# OSSILEDController.net
KiCad netlist of a schematic drawn in EAGLE
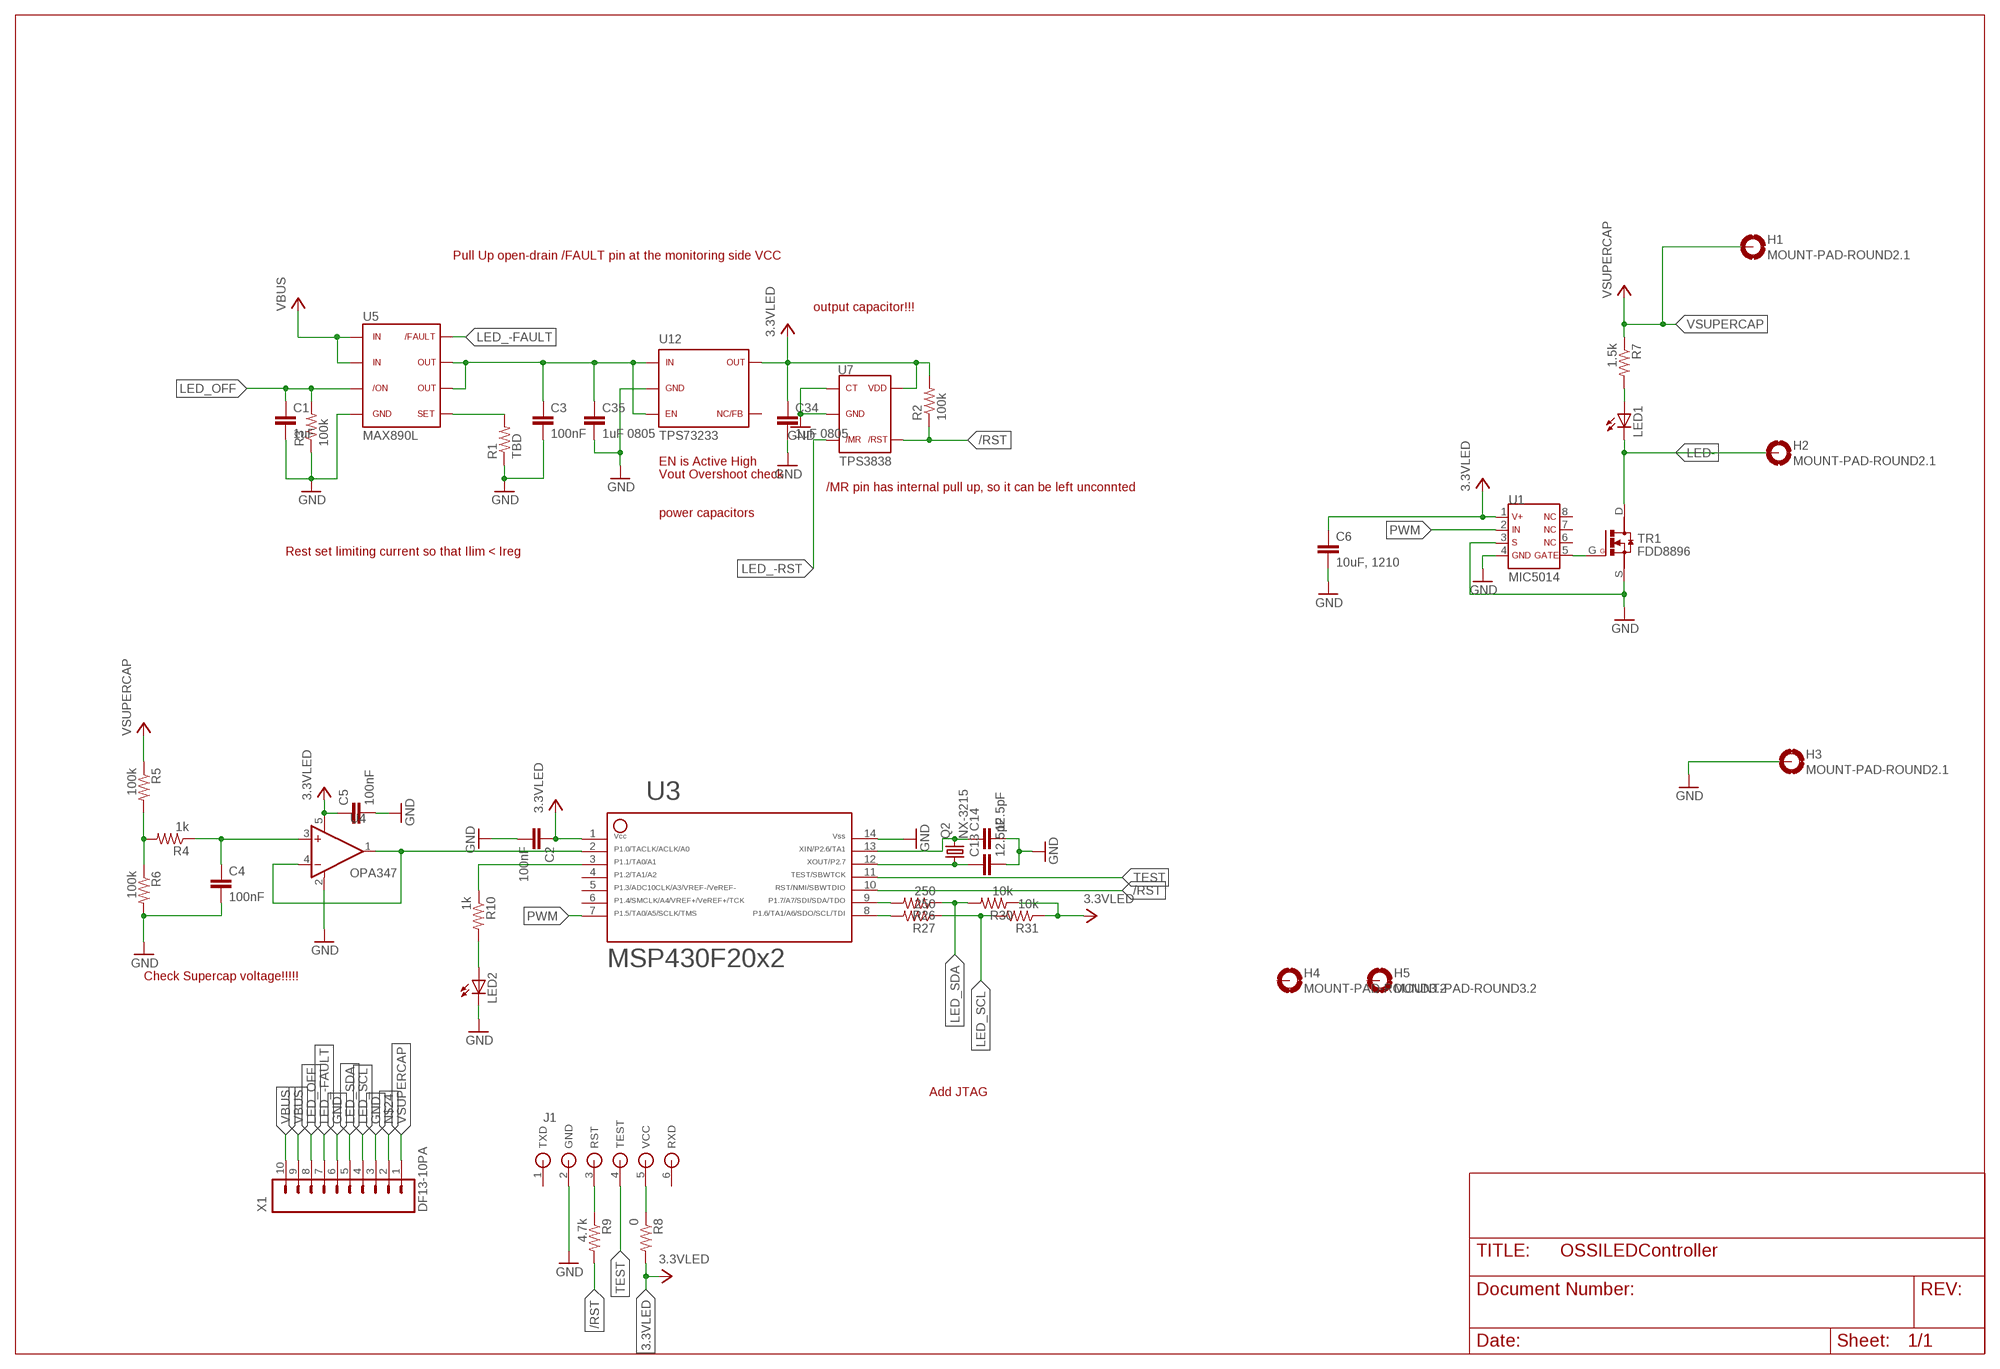
[diagram p0: schematic, sheet 1]

(export (version "E")
  (design (tool "Eeschema 10.0.6"))
  (components
    (comp (ref "C1")
      (value "1uF")
      (footprint "eagle-import:C0603(1608)")
      (libsource (lib "eagle-import") (part "C0603(1608)"))
    )
    (comp (ref "C2")
      (value "100nF")
      (footprint "eagle-import:C0603(1608)")
      (libsource (lib "eagle-import") (part "C0603(1608)"))
    )
    (comp (ref "C3")
      (value "100nF")
      (footprint "eagle-import:C0603(1608)")
      (libsource (lib "eagle-import") (part "C0603(1608)"))
    )
    (comp (ref "C4")
      (value "100nF")
      (footprint "eagle-import:C0603(1608)")
      (libsource (lib "eagle-import") (part "C0603(1608)"))
    )
    (comp (ref "C5")
      (value "100nF")
      (footprint "eagle-import:C0603(1608)")
      (libsource (lib "eagle-import") (part "C0603(1608)"))
    )
    (comp (ref "C6")
      (value "10uF, 1210")
      (footprint "eagle-import:C1210-GCM32")
      (libsource (lib "eagle-import") (part "C1210(3225)-GCM32"))
    )
    (comp (ref "C13")
      (value "12.5pF")
      (footprint "eagle-import:C0603(1608)")
      (libsource (lib "eagle-import") (part "C0603(1608)"))
    )
    (comp (ref "C14")
      (value "12.5pF")
      (footprint "eagle-import:C0603(1608)")
      (libsource (lib "eagle-import") (part "C0603(1608)"))
    )
    (comp (ref "C34")
      (value "1uF 0805")
      (footprint "eagle-import:C0805(2012)")
      (libsource (lib "eagle-import") (part "C0805(2012)"))
    )
    (comp (ref "C35")
      (value "1uF 0805")
      (footprint "eagle-import:C0805(2012)")
      (libsource (lib "eagle-import") (part "C0805(2012)"))
    )
    (comp (ref "H1")
      (value "MOUNT-PAD-ROUND2.1")
      (footprint "eagle-import:2.1-PAD-ROUND")
      (libsource (lib "eagle-import") (part "MOUNT-PAD-ROUND2.1"))
    )
    (comp (ref "H2")
      (value "MOUNT-PAD-ROUND2.1")
      (footprint "eagle-import:2.1-PAD-ROUND")
      (libsource (lib "eagle-import") (part "MOUNT-PAD-ROUND2.1"))
    )
    (comp (ref "H3")
      (value "MOUNT-PAD-ROUND2.1")
      (footprint "eagle-import:2.1-PAD-ROUND")
      (libsource (lib "eagle-import") (part "MOUNT-PAD-ROUND2.1"))
    )
    (comp (ref "H4")
      (value "MOUNT-PAD-ROUND3.2")
      (footprint "eagle-import:3.2-PAD-ROUND")
      (libsource (lib "eagle-import") (part "MOUNT-PAD-ROUND3.2"))
    )
    (comp (ref "H5")
      (value "MOUNT-PAD-ROUND3.2")
      (footprint "eagle-import:3.2-PAD-ROUND")
      (libsource (lib "eagle-import") (part "MOUNT-PAD-ROUND3.2"))
    )
    (comp (ref "J1")
      (value "JTAG-SBW-6")
      (footprint "eagle-import:SMD-PAD-6")
      (libsource (lib "eagle-import") (part "JTAG-SBW-6"))
    )
    (comp (ref "LED1")
      (value "LEDCHIPLED_0603")
      (footprint "eagle-import:CHIPLED_0603")
      (libsource (lib "eagle-import") (part "LEDCHIPLED_0603"))
    )
    (comp (ref "LED2")
      (value "LEDCHIPLED_0603")
      (footprint "eagle-import:CHIPLED_0603")
      (libsource (lib "eagle-import") (part "LEDCHIPLED_0603"))
    )
    (comp (ref "Q2")
      (value "NX-3215")
      (footprint "eagle-import:NX-3215")
      (libsource (lib "eagle-import") (part "NX-3215"))
    )
    (comp (ref "R1")
      (value "TBD")
      (footprint "eagle-import:R0603(1608)")
      (libsource (lib "eagle-import") (part "R0603(1608)"))
    )
    (comp (ref "R2")
      (value "100k")
      (footprint "eagle-import:R0603(1608)")
      (libsource (lib "eagle-import") (part "R0603(1608)"))
    )
    (comp (ref "R3")
      (value "100k")
      (footprint "eagle-import:R0603(1608)")
      (libsource (lib "eagle-import") (part "R0603(1608)"))
    )
    (comp (ref "R4")
      (value "1k")
      (footprint "eagle-import:R0603(1608)")
      (libsource (lib "eagle-import") (part "R0603(1608)"))
    )
    (comp (ref "R5")
      (value "100k")
      (footprint "eagle-import:R0603(1608)")
      (libsource (lib "eagle-import") (part "R0603(1608)"))
    )
    (comp (ref "R6")
      (value "100k")
      (footprint "eagle-import:R0603(1608)")
      (libsource (lib "eagle-import") (part "R0603(1608)"))
    )
    (comp (ref "R7")
      (value "1.5k")
      (footprint "eagle-import:R0603(1608)")
      (libsource (lib "eagle-import") (part "R0603(1608)"))
    )
    (comp (ref "R8")
      (value "0")
      (footprint "eagle-import:R0603(1608)")
      (libsource (lib "eagle-import") (part "R0603(1608)"))
    )
    (comp (ref "R9")
      (value "4.7k")
      (footprint "eagle-import:R0603(1608)")
      (libsource (lib "eagle-import") (part "R0603(1608)"))
    )
    (comp (ref "R10")
      (value "1k")
      (footprint "eagle-import:R0603(1608)")
      (libsource (lib "eagle-import") (part "R0603(1608)"))
    )
    (comp (ref "R26")
      (value "250")
      (footprint "eagle-import:R0603(1608)")
      (libsource (lib "eagle-import") (part "R0603(1608)"))
    )
    (comp (ref "R27")
      (value "250")
      (footprint "eagle-import:R0603(1608)")
      (libsource (lib "eagle-import") (part "R0603(1608)"))
    )
    (comp (ref "R30")
      (value "10k")
      (footprint "eagle-import:R0603(1608)")
      (libsource (lib "eagle-import") (part "R0603(1608)"))
    )
    (comp (ref "R31")
      (value "10k")
      (footprint "eagle-import:R0603(1608)")
      (libsource (lib "eagle-import") (part "R0603(1608)"))
    )
    (comp (ref "TR1")
      (value "FDD8896")
      (footprint "eagle-import:TO252")
      (libsource (lib "eagle-import") (part "FDD8896"))
    )
    (comp (ref "U1")
      (value "MIC5014")
      (footprint "eagle-import:SO8")
      (libsource (lib "eagle-import") (part "MIC5014"))
    )
    (comp (ref "U3")
      (value "MSP430F2012")
      (footprint "eagle-import:PW14")
      (libsource (lib "eagle-import") (part "MSP430F2012"))
    )
    (comp (ref "U4")
      (value "OPA347")
      (footprint "eagle-import:SOT23-5DBV")
      (libsource (lib "eagle-import") (part "OPA347"))
    )
    (comp (ref "U5")
      (value "MAX890L")
      (footprint "eagle-import:SO8")
      (libsource (lib "eagle-import") (part "MAX890L"))
    )
    (comp (ref "U7")
      (value "TPS3838")
      (footprint "eagle-import:SOT23-5DBV")
      (libsource (lib "eagle-import") (part "TPS3838"))
    )
    (comp (ref "U12")
      (value "TPS73233")
      (footprint "eagle-import:SOT23-5DBV")
      (libsource (lib "eagle-import") (part "TPS73233"))
    )
    (comp (ref "X1")
      (value "DF13-10PA")
      (footprint "eagle-import:DF13A-10P")
      (libsource (lib "eagle-import") (part "DF13-10PA"))
    )
  )
  (nets
    (net (code "1") (name "3.3VLED") (class "Default")
      (node (ref "C2") (pin "1") (pinfunction "1_1") (pintype "passive"))
      (node (ref "C34") (pin "1") (pinfunction "1_1") (pintype "passive"))
      (node (ref "C5") (pin "1") (pinfunction "1_1") (pintype "passive"))
      (node (ref "C6") (pin "P$1") (pinfunction "1_P$1") (pintype "passive"))
      (node (ref "R2") (pin "2") (pinfunction "2_2") (pintype "passive"))
      (node (ref "R30") (pin "1") (pinfunction "1_1") (pintype "passive"))
      (node (ref "R31") (pin "1") (pinfunction "1_1") (pintype "passive"))
      (node (ref "R8") (pin "2") (pinfunction "2_2") (pintype "passive"))
      (node (ref "U1") (pin "1") (pinfunction "P$1_1") (pintype "bidirectional"))
      (node (ref "U12") (pin "5") (pinfunction "5_5") (pintype "power_in"))
      (node (ref "U3") (pin "1") (pinfunction "1_1") (pintype "power_in"))
      (node (ref "U4") (pin "5") (pinfunction "V+_5") (pintype "power_in"))
      (node (ref "U7") (pin "5") (pinfunction "P$5_5") (pintype "power_in"))
    )
    (net (code "2") (name "GND") (class "Default")
      (node (ref "C1") (pin "2") (pinfunction "2_2") (pintype "passive"))
      (node (ref "C13") (pin "2") (pinfunction "2_2") (pintype "passive"))
      (node (ref "C14") (pin "2") (pinfunction "2_2") (pintype "passive"))
      (node (ref "C2") (pin "2") (pinfunction "2_2") (pintype "passive"))
      (node (ref "C3") (pin "2") (pinfunction "2_2") (pintype "passive"))
      (node (ref "C34") (pin "2") (pinfunction "2_2") (pintype "passive"))
      (node (ref "C35") (pin "2") (pinfunction "2_2") (pintype "passive"))
      (node (ref "C4") (pin "2") (pinfunction "2_2") (pintype "passive"))
      (node (ref "C5") (pin "2") (pinfunction "2_2") (pintype "passive"))
      (node (ref "C6") (pin "P$2") (pinfunction "2_P$2") (pintype "passive"))
      (node (ref "H3") (pin "B3,2") (pinfunction "MOUNT_B3,2") (pintype "passive"))
      (node (ref "J1") (pin "2") (pinfunction "GND_2") (pintype "bidirectional"))
      (node (ref "LED2") (pin "C") (pinfunction "C_C") (pintype "passive"))
      (node (ref "R1") (pin "1") (pinfunction "1_1") (pintype "passive"))
      (node (ref "R3") (pin "1") (pinfunction "1_1") (pintype "passive"))
      (node (ref "R6") (pin "2") (pinfunction "2_2") (pintype "passive"))
      (node (ref "TR1") (pin "S") (pinfunction "S_S") (pintype "bidirectional"))
      (node (ref "U1") (pin "3") (pinfunction "P$3_3") (pintype "bidirectional"))
      (node (ref "U1") (pin "4") (pinfunction "P$4_4") (pintype "bidirectional"))
      (node (ref "U12") (pin "2") (pinfunction "2_2") (pintype "power_in"))
      (node (ref "U3") (pin "14") (pinfunction "14_14") (pintype "power_in"))
      (node (ref "U4") (pin "2") (pinfunction "V-_2") (pintype "power_in"))
      (node (ref "U5") (pin "4") (pinfunction "P$4_4") (pintype "power_in"))
      (node (ref "U7") (pin "1") (pinfunction "P$1_1") (pintype "bidirectional"))
      (node (ref "U7") (pin "2") (pinfunction "P$2_2") (pintype "power_in"))
      (node (ref "X1") (pin "3") (pinfunction "3_3") (pintype "passive"))
      (node (ref "X1") (pin "6") (pinfunction "6_6") (pintype "passive"))
    )
    (net (code "3") (name "LED-") (class "Default")
      (node (ref "H2") (pin "B3,2") (pinfunction "MOUNT_B3,2") (pintype "passive"))
      (node (ref "LED1") (pin "C") (pinfunction "C_C") (pintype "passive"))
      (node (ref "TR1") (pin "D") (pinfunction "D_D") (pintype "bidirectional"))
    )
    (net (code "4") (name "LED_-FAULT") (class "Default")
      (node (ref "U5") (pin "8") (pinfunction "P$8_8") (pintype "output"))
      (node (ref "X1") (pin "7") (pinfunction "7_7") (pintype "passive"))
    )
    (net (code "5") (name "LED_-RST") (class "Default")
      (node (ref "U7") (pin "3") (pinfunction "P$3_3") (pintype "input"))
    )
    (net (code "6") (name "LED_OFF") (class "Default")
      (node (ref "C1") (pin "1") (pinfunction "1_1") (pintype "passive"))
      (node (ref "R3") (pin "2") (pinfunction "2_2") (pintype "passive"))
      (node (ref "U5") (pin "3") (pinfunction "P$3_3") (pintype "input"))
      (node (ref "X1") (pin "8") (pinfunction "8_8") (pintype "passive"))
    )
    (net (code "7") (name "LED_SCL") (class "Default")
      (node (ref "R27") (pin "1") (pinfunction "1_1") (pintype "passive"))
      (node (ref "R31") (pin "2") (pinfunction "2_2") (pintype "passive"))
      (node (ref "X1") (pin "4") (pinfunction "4_4") (pintype "passive"))
    )
    (net (code "8") (name "LED_SDA") (class "Default")
      (node (ref "R26") (pin "1") (pinfunction "1_1") (pintype "passive"))
      (node (ref "R30") (pin "2") (pinfunction "2_2") (pintype "passive"))
      (node (ref "X1") (pin "5") (pinfunction "5_5") (pintype "passive"))
    )
    (net (code "9") (name "N$24") (class "Default")
      (node (ref "X1") (pin "2") (pinfunction "2_2") (pintype "passive"))
    )
    (net (code "10") (name "Net-(C13-Pad1)") (class "Default")
      (node (ref "C13") (pin "1") (pinfunction "1_1") (pintype "passive"))
      (node (ref "Q2") (pin "1") (pinfunction "1_1") (pintype "passive"))
      (node (ref "U3") (pin "12") (pinfunction "12_12") (pintype "bidirectional"))
    )
    (net (code "11") (name "Net-(C14-Pad1)") (class "Default")
      (node (ref "C14") (pin "1") (pinfunction "1_1") (pintype "passive"))
      (node (ref "Q2") (pin "2") (pinfunction "2_2") (pintype "passive"))
      (node (ref "U3") (pin "13") (pinfunction "13_13") (pintype "bidirectional"))
    )
    (net (code "12") (name "Net-(J1-RST)") (class "Default")
      (node (ref "J1") (pin "3") (pinfunction "RST_3") (pintype "bidirectional"))
      (node (ref "R9") (pin "1") (pinfunction "1_1") (pintype "passive"))
    )
    (net (code "13") (name "Net-(J1-VCC)") (class "Default")
      (node (ref "J1") (pin "5") (pinfunction "VCC_5") (pintype "bidirectional"))
      (node (ref "R8") (pin "1") (pinfunction "1_1") (pintype "passive"))
    )
    (net (code "14") (name "Net-(LED1-PadA)") (class "Default")
      (node (ref "LED1") (pin "A") (pinfunction "A_A") (pintype "passive"))
      (node (ref "R7") (pin "2") (pinfunction "2_2") (pintype "passive"))
    )
    (net (code "15") (name "Net-(LED2-PadA)") (class "Default")
      (node (ref "LED2") (pin "A") (pinfunction "A_A") (pintype "passive"))
      (node (ref "R10") (pin "2") (pinfunction "2_2") (pintype "passive"))
    )
    (net (code "16") (name "Net-(R4-Pad2)") (class "Default")
      (node (ref "R4") (pin "2") (pinfunction "2_2") (pintype "passive"))
      (node (ref "R5") (pin "2") (pinfunction "2_2") (pintype "passive"))
      (node (ref "R6") (pin "1") (pinfunction "1_1") (pintype "passive"))
    )
    (net (code "17") (name "Net-(R10-Pad1)") (class "Default")
      (node (ref "R10") (pin "1") (pinfunction "1_1") (pintype "passive"))
      (node (ref "U3") (pin "3") (pinfunction "3_3") (pintype "bidirectional"))
    )
    (net (code "18") (name "Net-(R26-Pad2)") (class "Default")
      (node (ref "R26") (pin "2") (pinfunction "2_2") (pintype "passive"))
      (node (ref "U3") (pin "9") (pinfunction "9_9") (pintype "bidirectional"))
    )
    (net (code "19") (name "Net-(R27-Pad2)") (class "Default")
      (node (ref "R27") (pin "2") (pinfunction "2_2") (pintype "passive"))
      (node (ref "U3") (pin "8") (pinfunction "8_8") (pintype "bidirectional"))
    )
    (net (code "20") (name "Net-(U1-P$5)") (class "Default")
      (node (ref "TR1") (pin "G") (pinfunction "G_G") (pintype "bidirectional"))
      (node (ref "U1") (pin "5") (pinfunction "P$5_5") (pintype "bidirectional"))
    )
    (net (code "21") (name "Net-(U4-+IN)") (class "Default")
      (node (ref "C4") (pin "1") (pinfunction "1_1") (pintype "passive"))
      (node (ref "R4") (pin "1") (pinfunction "1_1") (pintype "passive"))
      (node (ref "U4") (pin "3") (pinfunction "+IN_3") (pintype "input"))
    )
    (net (code "22") (name "Net-(U4--IN)") (class "Default")
      (node (ref "U3") (pin "2") (pinfunction "2_2") (pintype "bidirectional"))
      (node (ref "U4") (pin "1") (pinfunction "OUT_1") (pintype "output"))
      (node (ref "U4") (pin "4") (pinfunction "-IN_4") (pintype "input"))
    )
    (net (code "23") (name "Net-(U5-P$5)") (class "Default")
      (node (ref "R1") (pin "2") (pinfunction "2_2") (pintype "passive"))
      (node (ref "U5") (pin "5") (pinfunction "P$5_5") (pintype "passive"))
    )
    (net (code "24") (name "Net-(U5-P$6)") (class "Default")
      (node (ref "C3") (pin "1") (pinfunction "1_1") (pintype "passive"))
      (node (ref "C35") (pin "1") (pinfunction "1_1") (pintype "passive"))
      (node (ref "U12") (pin "1") (pinfunction "1_1") (pintype "power_in"))
      (node (ref "U12") (pin "3") (pinfunction "3_3") (pintype "input"))
      (node (ref "U5") (pin "6") (pinfunction "P$6_6") (pintype "output"))
      (node (ref "U5") (pin "7") (pinfunction "P$7_7") (pintype "output"))
    )
    (net (code "25") (name "PWM") (class "Default")
      (node (ref "U1") (pin "2") (pinfunction "P$2_2") (pintype "bidirectional"))
      (node (ref "U3") (pin "7") (pinfunction "7_7") (pintype "bidirectional"))
    )
    (net (code "26") (name "TEST") (class "Default")
      (node (ref "J1") (pin "4") (pinfunction "TEST_4") (pintype "bidirectional"))
      (node (ref "U3") (pin "11") (pinfunction "11_11") (pintype "input"))
    )
    (net (code "27") (name "VBUS") (class "Default")
      (node (ref "U5") (pin "1") (pinfunction "P$1_1") (pintype "input"))
      (node (ref "U5") (pin "2") (pinfunction "P$2_2") (pintype "input"))
      (node (ref "X1") (pin "10") (pinfunction "10_10") (pintype "passive"))
      (node (ref "X1") (pin "9") (pinfunction "9_9") (pintype "passive"))
    )
    (net (code "28") (name "VSUPERCAP") (class "Default")
      (node (ref "H1") (pin "B3,2") (pinfunction "MOUNT_B3,2") (pintype "passive"))
      (node (ref "R5") (pin "1") (pinfunction "1_1") (pintype "passive"))
      (node (ref "R7") (pin "1") (pinfunction "1_1") (pintype "passive"))
      (node (ref "X1") (pin "1") (pinfunction "1_1") (pintype "passive"))
    )
    (net (code "29") (name "unconnected-(H4-MOUNT-PadB3,2)") (class "Default")
      (node (ref "H4") (pin "B3,2") (pinfunction "MOUNT_B3,2") (pintype "passive"))
    )
    (net (code "30") (name "unconnected-(H5-MOUNT-PadB3,2)") (class "Default")
      (node (ref "H5") (pin "B3,2") (pinfunction "MOUNT_B3,2") (pintype "passive"))
    )
    (net (code "31") (name "unconnected-(J1-RXD-Pad6)") (class "Default")
      (node (ref "J1") (pin "6") (pinfunction "RXD_6") (pintype "bidirectional"))
    )
    (net (code "32") (name "unconnected-(J1-TXD-Pad1)") (class "Default")
      (node (ref "J1") (pin "1") (pinfunction "TXD_1") (pintype "bidirectional"))
    )
    (net (code "33") (name "unconnected-(U1-P$6-Pad6)") (class "Default")
      (node (ref "U1") (pin "6") (pinfunction "P$6_6") (pintype "bidirectional"))
    )
    (net (code "34") (name "unconnected-(U1-P$7-Pad7)") (class "Default")
      (node (ref "U1") (pin "7") (pinfunction "P$7_7") (pintype "bidirectional"))
    )
    (net (code "35") (name "unconnected-(U1-P$8-Pad8)") (class "Default")
      (node (ref "U1") (pin "8") (pinfunction "P$8_8") (pintype "bidirectional"))
    )
    (net (code "36") (name "unconnected-(U3-Pad4)") (class "Default")
      (node (ref "U3") (pin "4") (pinfunction "4_4") (pintype "bidirectional"))
    )
    (net (code "37") (name "unconnected-(U3-Pad5)") (class "Default")
      (node (ref "U3") (pin "5") (pinfunction "5_5") (pintype "bidirectional"))
    )
    (net (code "38") (name "unconnected-(U3-Pad6)") (class "Default")
      (node (ref "U3") (pin "6") (pinfunction "6_6") (pintype "bidirectional"))
    )
    (net (code "39") (name "unconnected-(U12-Pad4)") (class "Default")
      (node (ref "U12") (pin "4") (pinfunction "4_4") (pintype "passive"))
    )
    (net (code "40") (name "{slash}RST") (class "Default")
      (node (ref "R2") (pin "1") (pinfunction "1_1") (pintype "passive"))
      (node (ref "R9") (pin "2") (pinfunction "2_2") (pintype "passive"))
      (node (ref "U3") (pin "10") (pinfunction "10_10") (pintype "bidirectional"))
      (node (ref "U7") (pin "4") (pinfunction "P$4_4") (pintype "output"))
    )
  )
)
